# Tempus_B.net
KiCad netlist of a schematic drawn in EAGLE
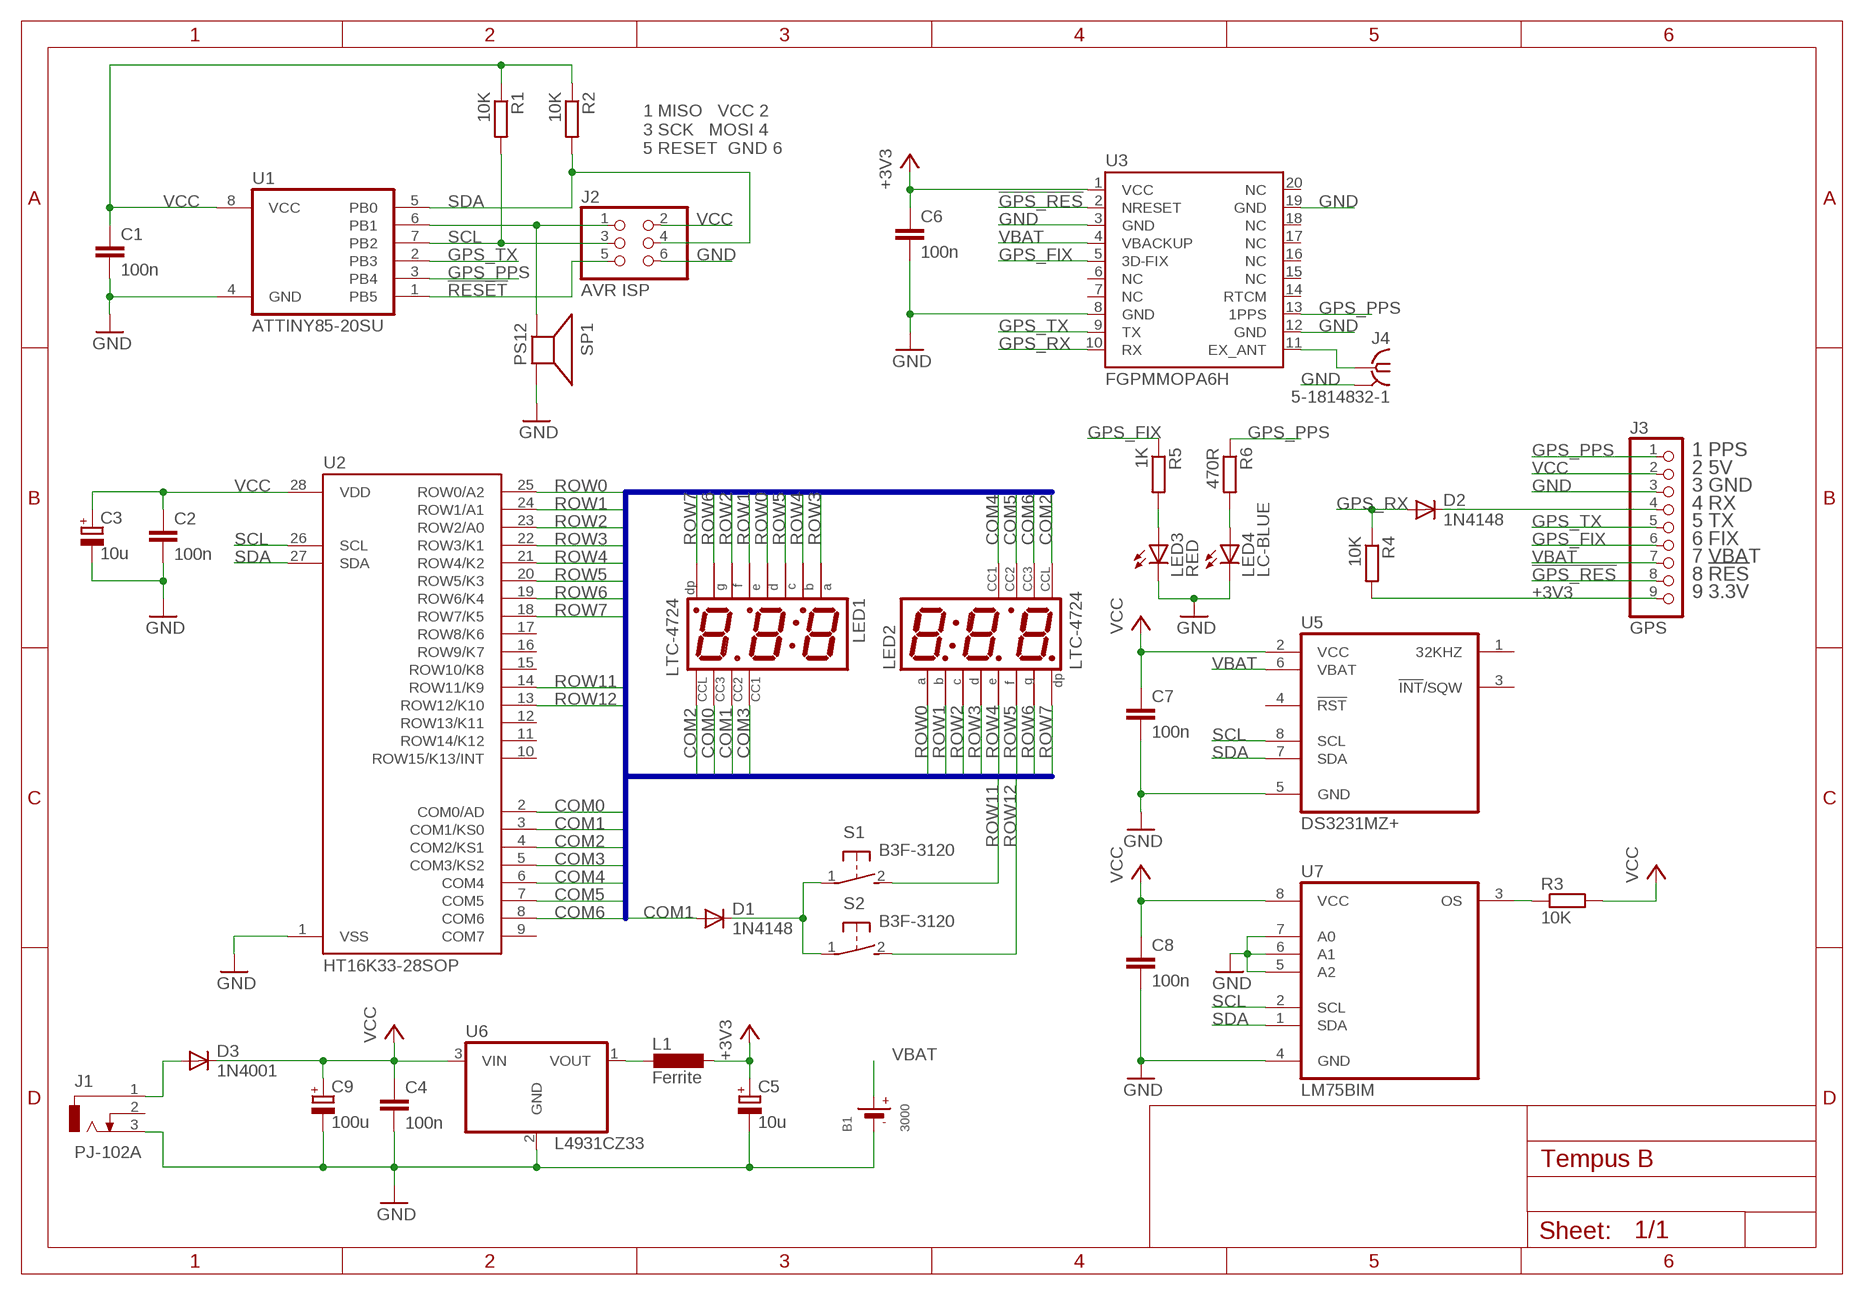
[diagram p0: schematic, sheet 1]

(export (version "E")
  (design (tool "Eeschema 10.0.6"))
  (components
    (comp (ref "B1")
      (value "3000")
      (footprint "eagle-import:CR1220")
      (libsource (lib "eagle-import") (part "BATTERYCR1220_SMT"))
    )
    (comp (ref "C1")
      (value "100n")
      (footprint "eagle-import:C1206")
      (libsource (lib "eagle-import") (part "C-EUC1206"))
    )
    (comp (ref "C2")
      (value "100n")
      (footprint "eagle-import:C1206")
      (libsource (lib "eagle-import") (part "C-EUC1206"))
    )
    (comp (ref "C3")
      (value "10u")
      (footprint "eagle-import:E2-5")
      (libsource (lib "eagle-import") (part "CPOL-EUE2-5"))
    )
    (comp (ref "C4")
      (value "100n")
      (footprint "eagle-import:C1206")
      (libsource (lib "eagle-import") (part "C-EUC1206"))
    )
    (comp (ref "C5")
      (value "10u")
      (footprint "eagle-import:E2-5")
      (libsource (lib "eagle-import") (part "CPOL-EUE2-5"))
    )
    (comp (ref "C6")
      (value "100n")
      (footprint "eagle-import:C1206")
      (libsource (lib "eagle-import") (part "C-EUC1206"))
    )
    (comp (ref "C7")
      (value "100n")
      (footprint "eagle-import:C1206")
      (libsource (lib "eagle-import") (part "C-EUC1206"))
    )
    (comp (ref "C8")
      (value "100n")
      (footprint "eagle-import:C1206")
      (libsource (lib "eagle-import") (part "C-EUC1206"))
    )
    (comp (ref "C9")
      (value "100u")
      (footprint "eagle-import:E2-5")
      (libsource (lib "eagle-import") (part "CPOL-EUE2-5"))
    )
    (comp (ref "D1")
      (value "1N4148")
      (footprint "eagle-import:DO35-10")
      (libsource (lib "eagle-import") (part "1N4148DO35-10"))
    )
    (comp (ref "D2")
      (value "1N4148")
      (footprint "eagle-import:DO35-10")
      (libsource (lib "eagle-import") (part "1N4148DO35-10"))
    )
    (comp (ref "D3")
      (value "1N4001")
      (footprint "eagle-import:DO41-10")
      (libsource (lib "eagle-import") (part "1N4004"))
    )
    (comp (ref "J1")
      (value "PJ-102A")
      (footprint "eagle-import:DCJACK-2.0MM")
      (libsource (lib "eagle-import") (part "DCJACK-2.0MM"))
    )
    (comp (ref "J2")
      (value "AVR ISP")
      (footprint "eagle-import:2X03")
      (libsource (lib "eagle-import") (part "PINHD-2X3"))
    )
    (comp (ref "J3")
      (value "GPS")
      (footprint "eagle-import:1X09")
      (libsource (lib "eagle-import") (part "PINHD-1X9"))
    )
    (comp (ref "J4")
      (value "5-1814832-1")
      (footprint "eagle-import:SMA-TH-ST")
      (libsource (lib "eagle-import") (part "SMA-TH-ST"))
    )
    (comp (ref "L1")
      (value "Ferrite")
      (footprint "eagle-import:L3216C")
      (libsource (lib "eagle-import") (part "L-EUL3216C"))
    )
    (comp (ref "LED1")
      (value "LTC-4724")
      (footprint "eagle-import:DIL15-LTC-4724")
      (libsource (lib "eagle-import") (part "LTC-4724"))
    )
    (comp (ref "LED2")
      (value "LTC-4724")
      (footprint "eagle-import:DIL15-LTC-4724")
      (libsource (lib "eagle-import") (part "LTC-4724"))
    )
    (comp (ref "LED3")
      (value "RED")
      (footprint "eagle-import:CHIPLED_1206")
      (libsource (lib "eagle-import") (part "LEDCHIPLED_1206"))
    )
    (comp (ref "LED4")
      (value "LC-BLUE")
      (footprint "eagle-import:CHIPLED_1206")
      (libsource (lib "eagle-import") (part "LEDCHIPLED_1206"))
    )
    (comp (ref "R1")
      (value "10K")
      (footprint "eagle-import:R1206")
      (libsource (lib "eagle-import") (part "R-EU_R1206"))
    )
    (comp (ref "R2")
      (value "10K")
      (footprint "eagle-import:R1206")
      (libsource (lib "eagle-import") (part "R-EU_R1206"))
    )
    (comp (ref "R3")
      (value "10K")
      (footprint "eagle-import:R1206")
      (libsource (lib "eagle-import") (part "R-EU_R1206"))
    )
    (comp (ref "R4")
      (value "10K")
      (footprint "eagle-import:R1206")
      (libsource (lib "eagle-import") (part "R-EU_R1206"))
    )
    (comp (ref "R5")
      (value "1K")
      (footprint "eagle-import:R1206")
      (libsource (lib "eagle-import") (part "R-EU_R1206"))
    )
    (comp (ref "R6")
      (value "470R")
      (footprint "eagle-import:R1206")
      (libsource (lib "eagle-import") (part "R-EU_R1206"))
    )
    (comp (ref "S1")
      (value "B3F-3120")
      (footprint "eagle-import:B3F-31XX")
      (fields (field (name "MPN") "B3F-3100"))
      (libsource (lib "eagle-import") (part "31-XX"))
    )
    (comp (ref "S2")
      (value "B3F-3120")
      (footprint "eagle-import:B3F-31XX")
      (fields (field (name "MPN") "B3F-3100"))
      (libsource (lib "eagle-import") (part "31-XX"))
    )
    (comp (ref "SP1")
      (value "PS12")
      (footprint "eagle-import:PS12")
      (libsource (lib "eagle-import") (part "SPEAKER/PS12"))
    )
    (comp (ref "U1")
      (value "ATTINY85-20SU")
      (footprint "eagle-import:SO08-EIAJ")
      (libsource (lib "eagle-import") (part "ATTINY85-20SU"))
    )
    (comp (ref "U2")
      (value "HT16K33-28SOP")
      (footprint "eagle-import:SO28W")
      (libsource (lib "eagle-import") (part "HT16K33-28SOP"))
    )
    (comp (ref "U3")
      (value "FGPMMOPA6H")
      (footprint "eagle-import:FGPMMOPA6H")
      (libsource (lib "eagle-import") (part "GPS_FGPMMOPA6H"))
    )
    (comp (ref "U5")
      (value "DS3231MZ+")
      (footprint "eagle-import:SO08")
      (libsource (lib "eagle-import") (part "DS3231MZ+"))
    )
    (comp (ref "U6")
      (value "L4931CZ33")
      (footprint "eagle-import:TO92-LINE")
      (libsource (lib "eagle-import") (part "L4931?CZ33"))
    )
    (comp (ref "U7")
      (value "LM75BIM")
      (footprint "eagle-import:SO08")
      (libsource (lib "eagle-import") (part "LM75BIM"))
    )
  )
  (nets
    (net (code "1") (name "+3V3") (class "Default")
      (node (ref "C5") (pin "+") (pinfunction "+_+") (pintype "passive"))
      (node (ref "C6") (pin "1") (pinfunction "1_1") (pintype "passive"))
      (node (ref "J3") (pin "9") (pinfunction "9_9") (pintype "passive"))
      (node (ref "L1") (pin "1") (pinfunction "1_1") (pintype "passive"))
      (node (ref "R4") (pin "2") (pinfunction "2_2") (pintype "passive"))
      (node (ref "U3") (pin "1") (pinfunction "VCC_1") (pintype "power_in"))
    )
    (net (code "2") (name "/COM0") (class "Default")
      (node (ref "LED1") (pin "7") (pinfunction "CC3_7") (pintype "passive"))
      (node (ref "U2") (pin "2") (pinfunction "COM0/AD_2") (pintype "bidirectional"))
    )
    (net (code "3") (name "/COM1") (class "Default")
      (node (ref "D1") (pin "A") (pinfunction "A_A") (pintype "passive"))
      (node (ref "LED1") (pin "5") (pinfunction "CC2_5") (pintype "passive"))
      (node (ref "U2") (pin "3") (pinfunction "COM1/KS0_3") (pintype "bidirectional"))
    )
    (net (code "4") (name "/COM2") (class "Default")
      (node (ref "LED1") (pin "14") (pinfunction "CCL_14") (pintype "passive"))
      (node (ref "LED2") (pin "14") (pinfunction "CCL_14") (pintype "passive"))
      (node (ref "U2") (pin "4") (pinfunction "COM2/KS1_4") (pintype "bidirectional"))
    )
    (net (code "5") (name "/COM3") (class "Default")
      (node (ref "LED1") (pin "1") (pinfunction "CC1_1") (pintype "passive"))
      (node (ref "U2") (pin "5") (pinfunction "COM3/KS2_5") (pintype "bidirectional"))
    )
    (net (code "6") (name "/COM4") (class "Default")
      (node (ref "LED2") (pin "1") (pinfunction "CC1_1") (pintype "passive"))
      (node (ref "U2") (pin "6") (pinfunction "COM4_6") (pintype "bidirectional"))
    )
    (net (code "7") (name "/COM5") (class "Default")
      (node (ref "LED2") (pin "5") (pinfunction "CC2_5") (pintype "passive"))
      (node (ref "U2") (pin "7") (pinfunction "COM5_7") (pintype "bidirectional"))
    )
    (net (code "8") (name "/COM6") (class "Default")
      (node (ref "LED2") (pin "7") (pinfunction "CC3_7") (pintype "passive"))
      (node (ref "U2") (pin "8") (pinfunction "COM6_8") (pintype "bidirectional"))
    )
    (net (code "9") (name "/GPS_FIX") (class "Default")
      (node (ref "J3") (pin "6") (pinfunction "6_6") (pintype "passive"))
      (node (ref "R5") (pin "1") (pinfunction "1_1") (pintype "passive"))
      (node (ref "U3") (pin "5") (pinfunction "3D-FIX_5") (pintype "output"))
    )
    (net (code "10") (name "/GPS_PPS") (class "Default")
      (node (ref "J3") (pin "1") (pinfunction "1_1") (pintype "passive"))
      (node (ref "R6") (pin "1") (pinfunction "1_1") (pintype "passive"))
      (node (ref "U1") (pin "3") (pinfunction "PB4_3") (pintype "bidirectional"))
      (node (ref "U3") (pin "13") (pinfunction "1PPS_13") (pintype "output"))
    )
    (net (code "11") (name "/GPS_RX") (class "Default")
      (node (ref "D2") (pin "A") (pinfunction "A_A") (pintype "passive"))
      (node (ref "R4") (pin "1") (pinfunction "1_1") (pintype "passive"))
      (node (ref "U3") (pin "10") (pinfunction "RX_10") (pintype "input"))
    )
    (net (code "12") (name "/GPS_TX") (class "Default")
      (node (ref "J3") (pin "5") (pinfunction "5_5") (pintype "passive"))
      (node (ref "U1") (pin "2") (pinfunction "PB3_2") (pintype "bidirectional"))
      (node (ref "U3") (pin "9") (pinfunction "TX_9") (pintype "output"))
    )
    (net (code "13") (name "/ROW0") (class "Default")
      (node (ref "LED1") (pin "4") (pinfunction "D_4") (pintype "passive"))
      (node (ref "LED2") (pin "12") (pinfunction "A_12") (pintype "passive"))
      (node (ref "U2") (pin "25") (pinfunction "ROW0/A2_25") (pintype "bidirectional"))
    )
    (net (code "14") (name "/ROW1") (class "Default")
      (node (ref "LED1") (pin "2") (pinfunction "E_2") (pintype "passive"))
      (node (ref "LED2") (pin "11") (pinfunction "B_11") (pintype "passive"))
      (node (ref "U2") (pin "24") (pinfunction "ROW1/A1_24") (pintype "bidirectional"))
    )
    (net (code "15") (name "/ROW2") (class "Default")
      (node (ref "LED1") (pin "15") (pinfunction "F_15") (pintype "passive"))
      (node (ref "LED2") (pin "3") (pinfunction "C_3") (pintype "passive"))
      (node (ref "U2") (pin "23") (pinfunction "ROW2/A0_23") (pintype "bidirectional"))
    )
    (net (code "16") (name "/ROW3") (class "Default")
      (node (ref "LED1") (pin "12") (pinfunction "A_12") (pintype "passive"))
      (node (ref "LED2") (pin "4") (pinfunction "D_4") (pintype "passive"))
      (node (ref "U2") (pin "22") (pinfunction "ROW3/K1_22") (pintype "bidirectional"))
    )
    (net (code "17") (name "/ROW4") (class "Default")
      (node (ref "LED1") (pin "11") (pinfunction "B_11") (pintype "passive"))
      (node (ref "LED2") (pin "2") (pinfunction "E_2") (pintype "passive"))
      (node (ref "U2") (pin "21") (pinfunction "ROW4/K2_21") (pintype "bidirectional"))
    )
    (net (code "18") (name "/ROW5") (class "Default")
      (node (ref "LED1") (pin "3") (pinfunction "C_3") (pintype "passive"))
      (node (ref "LED2") (pin "15") (pinfunction "F_15") (pintype "passive"))
      (node (ref "U2") (pin "20") (pinfunction "ROW5/K3_20") (pintype "bidirectional"))
    )
    (net (code "19") (name "/ROW6") (class "Default")
      (node (ref "LED1") (pin "8") (pinfunction "G_8") (pintype "passive"))
      (node (ref "LED2") (pin "8") (pinfunction "G_8") (pintype "passive"))
      (node (ref "U2") (pin "19") (pinfunction "ROW6/K4_19") (pintype "bidirectional"))
    )
    (net (code "20") (name "/ROW7") (class "Default")
      (node (ref "LED1") (pin "6") (pinfunction "DP_6") (pintype "passive"))
      (node (ref "LED2") (pin "6") (pinfunction "DP_6") (pintype "passive"))
      (node (ref "U2") (pin "18") (pinfunction "ROW7/K5_18") (pintype "bidirectional"))
    )
    (net (code "21") (name "/ROW11") (class "Default")
      (node (ref "S1") (pin "2") (pinfunction "S_2") (pintype "passive"))
      (node (ref "U2") (pin "14") (pinfunction "ROW11/K9_14") (pintype "bidirectional"))
    )
    (net (code "22") (name "/ROW12") (class "Default")
      (node (ref "S2") (pin "2") (pinfunction "S_2") (pintype "passive"))
      (node (ref "U2") (pin "13") (pinfunction "ROW12/K10_13") (pintype "bidirectional"))
    )
    (net (code "23") (name "/SCL") (class "Default")
      (node (ref "J2") (pin "3") (pinfunction "3_3") (pintype "passive"))
      (node (ref "R1") (pin "2") (pinfunction "2_2") (pintype "passive"))
      (node (ref "U1") (pin "7") (pinfunction "PB2_7") (pintype "bidirectional"))
      (node (ref "U2") (pin "26") (pinfunction "SCL_26") (pintype "input"))
      (node (ref "U5") (pin "8") (pinfunction "SCL_8") (pintype "input"))
      (node (ref "U7") (pin "2") (pinfunction "SCL_2") (pintype "input"))
    )
    (net (code "24") (name "/SDA") (class "Default")
      (node (ref "J2") (pin "4") (pinfunction "4_4") (pintype "passive"))
      (node (ref "R2") (pin "2") (pinfunction "2_2") (pintype "passive"))
      (node (ref "U1") (pin "5") (pinfunction "PB0_5") (pintype "bidirectional"))
      (node (ref "U2") (pin "27") (pinfunction "SDA_27") (pintype "bidirectional"))
      (node (ref "U5") (pin "7") (pinfunction "SDA_7") (pintype "bidirectional"))
      (node (ref "U7") (pin "1") (pinfunction "SDA_1") (pintype "bidirectional"))
    )
    (net (code "25") (name "/VBAT") (class "Default")
      (node (ref "B1") (pin "+$1") (pinfunction "+_+$1") (pintype "passive"))
      (node (ref "J3") (pin "7") (pinfunction "7_7") (pintype "passive"))
      (node (ref "U3") (pin "4") (pinfunction "VBACKUP_4") (pintype "power_in"))
      (node (ref "U5") (pin "6") (pinfunction "VBAT_6") (pintype "power_in"))
    )
    (net (code "26") (name "/~{GPS_RES}") (class "Default")
      (node (ref "J3") (pin "8") (pinfunction "8_8") (pintype "passive"))
      (node (ref "U3") (pin "2") (pinfunction "NRESET_2") (pintype "input"))
    )
    (net (code "27") (name "/~{RESET}") (class "Default")
      (node (ref "J2") (pin "5") (pinfunction "5_5") (pintype "passive"))
      (node (ref "U1") (pin "1") (pinfunction "PB5_1") (pintype "bidirectional"))
    )
    (net (code "28") (name "GND") (class "Default")
      (node (ref "B1") (pin "-") (pinfunction "-_-") (pintype "passive"))
      (node (ref "C1") (pin "2") (pinfunction "2_2") (pintype "passive"))
      (node (ref "C2") (pin "2") (pinfunction "2_2") (pintype "passive"))
      (node (ref "C3") (pin "-") (pinfunction "-_-") (pintype "passive"))
      (node (ref "C4") (pin "2") (pinfunction "2_2") (pintype "passive"))
      (node (ref "C5") (pin "-") (pinfunction "-_-") (pintype "passive"))
      (node (ref "C6") (pin "2") (pinfunction "2_2") (pintype "passive"))
      (node (ref "C7") (pin "2") (pinfunction "2_2") (pintype "passive"))
      (node (ref "C8") (pin "2") (pinfunction "2_2") (pintype "passive"))
      (node (ref "C9") (pin "-") (pinfunction "-_-") (pintype "passive"))
      (node (ref "J1") (pin "3") (pinfunction "3_3") (pintype "passive"))
      (node (ref "J2") (pin "6") (pinfunction "6_6") (pintype "passive"))
      (node (ref "J3") (pin "3") (pinfunction "3_3") (pintype "passive"))
      (node (ref "J4") (pin "2") (pinfunction "2_2") (pintype "passive"))
      (node (ref "J4") (pin "3") (pinfunction "2_3") (pintype "passive"))
      (node (ref "J4") (pin "4") (pinfunction "2_4") (pintype "passive"))
      (node (ref "J4") (pin "5") (pinfunction "2_5") (pintype "passive"))
      (node (ref "LED3") (pin "C") (pinfunction "C_C") (pintype "passive"))
      (node (ref "LED4") (pin "C") (pinfunction "C_C") (pintype "passive"))
      (node (ref "SP1") (pin "P$2") (pinfunction "-_P$2") (pintype "passive"))
      (node (ref "U1") (pin "4") (pinfunction "GND_4") (pintype "power_in"))
      (node (ref "U2") (pin "1") (pinfunction "VSS_1") (pintype "power_in"))
      (node (ref "U3") (pin "12") (pinfunction "GND_12") (pintype "power_in"))
      (node (ref "U3") (pin "19") (pinfunction "GND_19") (pintype "power_in"))
      (node (ref "U3") (pin "3") (pinfunction "GND_3") (pintype "power_in"))
      (node (ref "U3") (pin "8") (pinfunction "GND_8") (pintype "power_in"))
      (node (ref "U5") (pin "5") (pinfunction "GND_5") (pintype "power_in"))
      (node (ref "U6") (pin "2") (pinfunction "GND_2") (pintype "power_in"))
      (node (ref "U7") (pin "4") (pinfunction "GND_4") (pintype "power_in"))
      (node (ref "U7") (pin "5") (pinfunction "A2_5") (pintype "input"))
      (node (ref "U7") (pin "6") (pinfunction "A1_6") (pintype "input"))
      (node (ref "U7") (pin "7") (pinfunction "A0_7") (pintype "input"))
    )
    (net (code "29") (name "Net-(D2-PadC)") (class "Default")
      (node (ref "D2") (pin "C") (pinfunction "C_C") (pintype "passive"))
      (node (ref "J3") (pin "4") (pinfunction "4_4") (pintype "passive"))
    )
    (net (code "30") (name "Net-(D3-PadA)") (class "Default")
      (node (ref "D3") (pin "A") (pinfunction "A_A") (pintype "passive"))
      (node (ref "J1") (pin "1") (pinfunction "1_1") (pintype "passive"))
    )
    (net (code "31") (name "Net-(LED3-PadA)") (class "Default")
      (node (ref "LED3") (pin "A") (pinfunction "A_A") (pintype "passive"))
      (node (ref "R5") (pin "2") (pinfunction "2_2") (pintype "passive"))
    )
    (net (code "32") (name "Net-(LED4-PadA)") (class "Default")
      (node (ref "LED4") (pin "A") (pinfunction "A_A") (pintype "passive"))
      (node (ref "R6") (pin "2") (pinfunction "2_2") (pintype "passive"))
    )
    (net (code "33") (name "Net-(S1-P)") (class "Default")
      (node (ref "D1") (pin "C") (pinfunction "C_C") (pintype "passive"))
      (node (ref "S1") (pin "1") (pinfunction "P_1") (pintype "passive"))
      (node (ref "S2") (pin "1") (pinfunction "P_1") (pintype "passive"))
    )
    (net (code "34") (name "Net-(SP1-+)") (class "Default")
      (node (ref "J2") (pin "1") (pinfunction "1_1") (pintype "passive"))
      (node (ref "SP1") (pin "P$1") (pinfunction "+_P$1") (pintype "passive"))
      (node (ref "U1") (pin "6") (pinfunction "PB1_6") (pintype "bidirectional"))
    )
    (net (code "35") (name "Net-(U3-EX_ANT)") (class "Default")
      (node (ref "J4") (pin "1") (pinfunction "1_1") (pintype "passive"))
      (node (ref "U3") (pin "11") (pinfunction "EX_ANT_11") (pintype "input"))
    )
    (net (code "36") (name "Net-(U6-VOUT)") (class "Default")
      (node (ref "L1") (pin "2") (pinfunction "2_2") (pintype "passive"))
      (node (ref "U6") (pin "1") (pinfunction "VOUT_1") (pintype "passive"))
    )
    (net (code "37") (name "Net-(U7-OS)") (class "Default")
      (node (ref "R3") (pin "1") (pinfunction "1_1") (pintype "passive"))
      (node (ref "U7") (pin "3") (pinfunction "OS_3") (pintype "open_collector"))
    )
    (net (code "38") (name "VCC") (class "Default")
      (node (ref "C1") (pin "1") (pinfunction "1_1") (pintype "passive"))
      (node (ref "C2") (pin "1") (pinfunction "1_1") (pintype "passive"))
      (node (ref "C3") (pin "+") (pinfunction "+_+") (pintype "passive"))
      (node (ref "C4") (pin "1") (pinfunction "1_1") (pintype "passive"))
      (node (ref "C7") (pin "1") (pinfunction "1_1") (pintype "passive"))
      (node (ref "C8") (pin "1") (pinfunction "1_1") (pintype "passive"))
      (node (ref "C9") (pin "+") (pinfunction "+_+") (pintype "passive"))
      (node (ref "D3") (pin "C") (pinfunction "C_C") (pintype "passive"))
      (node (ref "J2") (pin "2") (pinfunction "2_2") (pintype "passive"))
      (node (ref "J3") (pin "2") (pinfunction "2_2") (pintype "passive"))
      (node (ref "R1") (pin "1") (pinfunction "1_1") (pintype "passive"))
      (node (ref "R2") (pin "1") (pinfunction "1_1") (pintype "passive"))
      (node (ref "R3") (pin "2") (pinfunction "2_2") (pintype "passive"))
      (node (ref "U1") (pin "8") (pinfunction "VCC_8") (pintype "power_in"))
      (node (ref "U2") (pin "28") (pinfunction "VDD_28") (pintype "power_in"))
      (node (ref "U5") (pin "2") (pinfunction "VCC_2") (pintype "power_in"))
      (node (ref "U6") (pin "3") (pinfunction "VIN_3") (pintype "power_in"))
      (node (ref "U7") (pin "8") (pinfunction "VCC_8") (pintype "power_in"))
    )
    (net (code "39") (name "unconnected-(J1-Pad2)") (class "Default")
      (node (ref "J1") (pin "2") (pinfunction "2_2") (pintype "passive"))
    )
    (net (code "40") (name "unconnected-(U2-COM7-Pad9)") (class "Default")
      (node (ref "U2") (pin "9") (pinfunction "COM7_9") (pintype "bidirectional"))
    )
    (net (code "41") (name "unconnected-(U2-ROW8{slash}K6-Pad17)") (class "Default")
      (node (ref "U2") (pin "17") (pinfunction "ROW8/K6_17") (pintype "bidirectional"))
    )
    (net (code "42") (name "unconnected-(U2-ROW9{slash}K7-Pad16)") (class "Default")
      (node (ref "U2") (pin "16") (pinfunction "ROW9/K7_16") (pintype "bidirectional"))
    )
    (net (code "43") (name "unconnected-(U2-ROW10{slash}K8-Pad15)") (class "Default")
      (node (ref "U2") (pin "15") (pinfunction "ROW10/K8_15") (pintype "bidirectional"))
    )
    (net (code "44") (name "unconnected-(U2-ROW13{slash}K11-Pad12)") (class "Default")
      (node (ref "U2") (pin "12") (pinfunction "ROW13/K11_12") (pintype "bidirectional"))
    )
    (net (code "45") (name "unconnected-(U2-ROW14{slash}K12-Pad11)") (class "Default")
      (node (ref "U2") (pin "11") (pinfunction "ROW14/K12_11") (pintype "bidirectional"))
    )
    (net (code "46") (name "unconnected-(U2-ROW15{slash}K13{slash}INT-Pad10)") (class "Default")
      (node (ref "U2") (pin "10") (pinfunction "ROW15/K13/INT_10") (pintype "bidirectional"))
    )
    (net (code "47") (name "unconnected-(U3-NC-Pad6)") (class "Default")
      (node (ref "U3") (pin "6") (pinfunction "NC_6") (pintype "no_connect"))
    )
    (net (code "48") (name "unconnected-(U3-NC-Pad7)") (class "Default")
      (node (ref "U3") (pin "7") (pinfunction "NC_7") (pintype "no_connect"))
    )
    (net (code "49") (name "unconnected-(U3-NC-Pad15)") (class "Default")
      (node (ref "U3") (pin "15") (pinfunction "NC_15") (pintype "no_connect"))
    )
    (net (code "50") (name "unconnected-(U3-NC-Pad16)") (class "Default")
      (node (ref "U3") (pin "16") (pinfunction "NC_16") (pintype "no_connect"))
    )
    (net (code "51") (name "unconnected-(U3-NC-Pad17)") (class "Default")
      (node (ref "U3") (pin "17") (pinfunction "NC_17") (pintype "no_connect"))
    )
    (net (code "52") (name "unconnected-(U3-NC-Pad18)") (class "Default")
      (node (ref "U3") (pin "18") (pinfunction "NC_18") (pintype "no_connect"))
    )
    (net (code "53") (name "unconnected-(U3-NC-Pad20)") (class "Default")
      (node (ref "U3") (pin "20") (pinfunction "NC_20") (pintype "no_connect"))
    )
    (net (code "54") (name "unconnected-(U3-RTCM-Pad14)") (class "Default")
      (node (ref "U3") (pin "14") (pinfunction "RTCM_14") (pintype "input"))
    )
    (net (code "55") (name "unconnected-(U5-32KHZ-Pad1)") (class "Default")
      (node (ref "U5") (pin "1") (pinfunction "32KHZ_1") (pintype "open_collector"))
    )
    (net (code "56") (name "unconnected-(U5-~{INT}{slash}SQW-Pad3)") (class "Default")
      (node (ref "U5") (pin "3") (pinfunction "~{INT}/SQW_3") (pintype "open_collector"))
    )
    (net (code "57") (name "unconnected-(U5-~{RST}-Pad4)") (class "Default")
      (node (ref "U5") (pin "4") (pinfunction "~{RST}_4") (pintype "bidirectional"))
    )
  )
)
